# power_regulator_pmic.net
KiCad netlist of a schematic drawn in Altium Designer
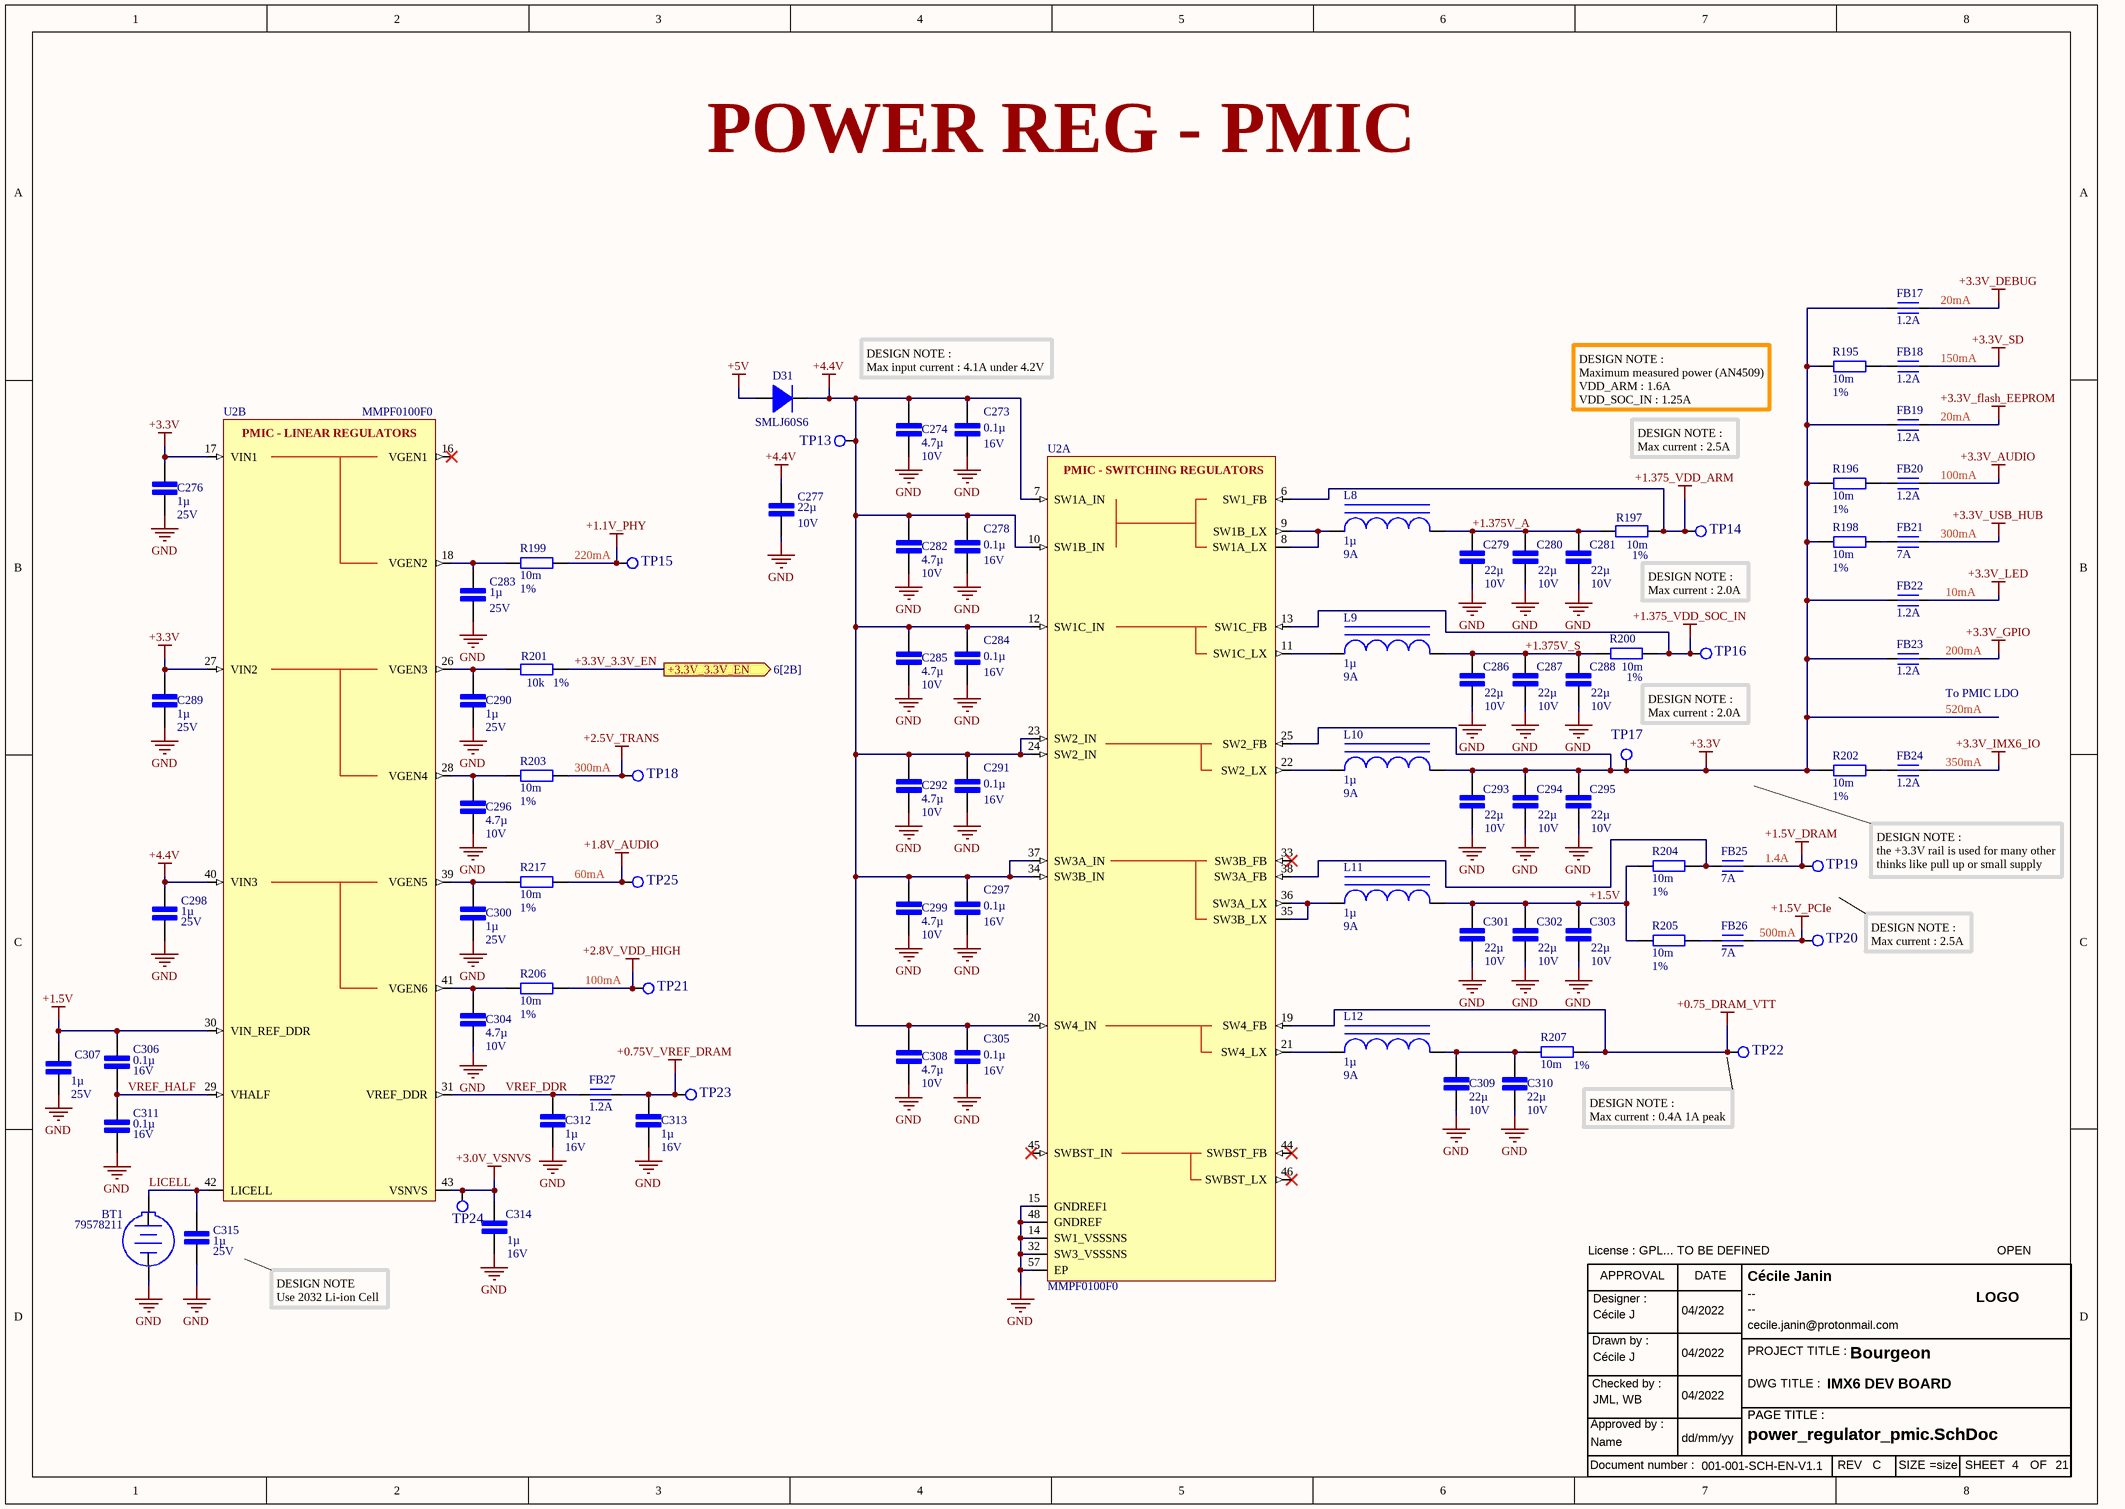
[diagram p0: power_regulator_pmic.SchDoc]

(export (version "E")
  (design (tool "Eeschema 10.0.6"))
  (components
    (comp (ref "BT1")
      (value "79578211")
      (footprint "Battery holder")
      (description "WA-BCPH Battery Holder, THT, Battery Type 2450")
      (fields (field (name "MANUFACTURER") "Wurth Elektronik"))
      (libsource (lib "First Board IMX6") (part "battery holder"))
    )
    (comp (ref "C273")
      (value "0.1µ")
      (footprint "Cap cer 0402/1005")
      (description "cap cer 0.1µ 16V 10% X7R 0402")
      (fields (field (name "TENSION DU DIÉLECTRIQUE") "16V"))
      (libsource (lib "First Board IMX6") (part "cap 0.1µ 4V"))
    )
    (comp (ref "C274")
      (value "4.7µ")
      (footprint "Cap cer 0402/1005")
      (description "cap cer 4.7µ 10V 10% X7R 0402")
      (fields (field (name "TENSION DU DIÉLECTRIQUE") "10V"))
      (libsource (lib "First Board IMX6") (part "cap 4.7µ 10V"))
    )
    (comp (ref "C276")
      (value "1µ")
      (footprint "Cap cer 0402/1005")
      (description "cap cer 1µ 25V 10% X5R 0402")
      (fields (field (name "TENSION DU DIÉLECTRIQUE") "25V"))
      (libsource (lib "First Board IMX6") (part "cap 1µ 25V"))
    )
    (comp (ref "C277")
      (value "22µ")
      (footprint "Cap cer 0603/4608")
      (description "cap cer 22µ 10V 10% X5R 0603")
      (fields (field (name "TENSION DU DIÉLECTRIQUE") "10V"))
      (libsource (lib "First Board IMX6") (part "cap 22µ 10V"))
    )
    (comp (ref "C278")
      (value "0.1µ")
      (footprint "Cap cer 0402/1005")
      (description "cap cer 0.1µ 16V 10% X7R 0402")
      (fields (field (name "TENSION DU DIÉLECTRIQUE") "16V"))
      (libsource (lib "First Board IMX6") (part "cap 0.1µ 4V"))
    )
    (comp (ref "C279")
      (value "22µ")
      (footprint "Cap cer 0603/4608")
      (description "cap cer 22µ 10V 10% X5R 0603")
      (fields (field (name "TENSION DU DIÉLECTRIQUE") "10V"))
      (libsource (lib "First Board IMX6") (part "cap 22µ 10V"))
    )
    (comp (ref "C280")
      (value "22µ")
      (footprint "Cap cer 0603/4608")
      (description "cap cer 22µ 10V 10% X5R 0603")
      (fields (field (name "TENSION DU DIÉLECTRIQUE") "10V"))
      (libsource (lib "First Board IMX6") (part "cap 22µ 10V"))
    )
    (comp (ref "C281")
      (value "22µ")
      (footprint "Cap cer 0603/4608")
      (description "cap cer 22µ 10V 10% X5R 0603")
      (fields (field (name "TENSION DU DIÉLECTRIQUE") "10V"))
      (libsource (lib "First Board IMX6") (part "cap 22µ 10V"))
    )
    (comp (ref "C282")
      (value "4.7µ")
      (footprint "Cap cer 0402/1005")
      (description "cap cer 4.7µ 10V 10% X7R 0402")
      (fields (field (name "TENSION DU DIÉLECTRIQUE") "10V"))
      (libsource (lib "First Board IMX6") (part "cap 4.7µ 10V"))
    )
    (comp (ref "C283")
      (value "1µ")
      (footprint "Cap cer 0402/1005")
      (description "cap cer 1µ 25V 10% X5R 0402")
      (fields (field (name "TENSION DU DIÉLECTRIQUE") "25V"))
      (libsource (lib "First Board IMX6") (part "cap 1µ 25V"))
    )
    (comp (ref "C284")
      (value "0.1µ")
      (footprint "Cap cer 0402/1005")
      (description "cap cer 0.1µ 16V 10% X7R 0402")
      (fields (field (name "TENSION DU DIÉLECTRIQUE") "16V"))
      (libsource (lib "First Board IMX6") (part "cap 0.1µ 4V"))
    )
    (comp (ref "C285")
      (value "4.7µ")
      (footprint "Cap cer 0402/1005")
      (description "cap cer 4.7µ 10V 10% X7R 0402")
      (fields (field (name "TENSION DU DIÉLECTRIQUE") "10V"))
      (libsource (lib "First Board IMX6") (part "cap 4.7µ 10V"))
    )
    (comp (ref "C286")
      (value "22µ")
      (footprint "Cap cer 0603/4608")
      (description "cap cer 22µ 10V 10% X5R 0603")
      (fields (field (name "TENSION DU DIÉLECTRIQUE") "10V"))
      (libsource (lib "First Board IMX6") (part "cap 22µ 10V"))
    )
    (comp (ref "C287")
      (value "22µ")
      (footprint "Cap cer 0603/4608")
      (description "cap cer 22µ 10V 10% X5R 0603")
      (fields (field (name "TENSION DU DIÉLECTRIQUE") "10V"))
      (libsource (lib "First Board IMX6") (part "cap 22µ 10V"))
    )
    (comp (ref "C288")
      (value "22µ")
      (footprint "Cap cer 0603/4608")
      (description "cap cer 22µ 10V 10% X5R 0603")
      (fields (field (name "TENSION DU DIÉLECTRIQUE") "10V"))
      (libsource (lib "First Board IMX6") (part "cap 22µ 10V"))
    )
    (comp (ref "C289")
      (value "1µ")
      (footprint "Cap cer 0402/1005")
      (description "cap cer 1µ 25V 10% X5R 0402")
      (fields (field (name "TENSION DU DIÉLECTRIQUE") "25V"))
      (libsource (lib "First Board IMX6") (part "cap 1µ 25V"))
    )
    (comp (ref "C290")
      (value "1µ")
      (footprint "Cap cer 0402/1005")
      (description "cap cer 1µ 25V 10% X5R 0402")
      (fields (field (name "TENSION DU DIÉLECTRIQUE") "25V"))
      (libsource (lib "First Board IMX6") (part "cap 1µ 25V"))
    )
    (comp (ref "C291")
      (value "0.1µ")
      (footprint "Cap cer 0402/1005")
      (description "cap cer 0.1µ 16V 10% X7R 0402")
      (fields (field (name "TENSION DU DIÉLECTRIQUE") "16V"))
      (libsource (lib "First Board IMX6") (part "cap 0.1µ 4V"))
    )
    (comp (ref "C292")
      (value "4.7µ")
      (footprint "Cap cer 0402/1005")
      (description "cap cer 4.7µ 10V 10% X7R 0402")
      (fields (field (name "TENSION DU DIÉLECTRIQUE") "10V"))
      (libsource (lib "First Board IMX6") (part "cap 4.7µ 10V"))
    )
    (comp (ref "C293")
      (value "22µ")
      (footprint "Cap cer 0603/4608")
      (description "cap cer 22µ 10V 10% X5R 0603")
      (fields (field (name "TENSION DU DIÉLECTRIQUE") "10V"))
      (libsource (lib "First Board IMX6") (part "cap 22µ 10V"))
    )
    (comp (ref "C294")
      (value "22µ")
      (footprint "Cap cer 0603/4608")
      (description "cap cer 22µ 10V 10% X5R 0603")
      (fields (field (name "TENSION DU DIÉLECTRIQUE") "10V"))
      (libsource (lib "First Board IMX6") (part "cap 22µ 10V"))
    )
    (comp (ref "C295")
      (value "22µ")
      (footprint "Cap cer 0603/4608")
      (description "cap cer 22µ 10V 10% X5R 0603")
      (fields (field (name "TENSION DU DIÉLECTRIQUE") "10V"))
      (libsource (lib "First Board IMX6") (part "cap 22µ 10V"))
    )
    (comp (ref "C296")
      (value "4.7µ")
      (footprint "Cap cer 0402/1005")
      (description "cap cer 4.7µ 10V 10% X7R 0402")
      (fields (field (name "TENSION DU DIÉLECTRIQUE") "10V"))
      (libsource (lib "First Board IMX6") (part "cap 4.7µ 10V"))
    )
    (comp (ref "C297")
      (value "0.1µ")
      (footprint "Cap cer 0402/1005")
      (description "cap cer 0.1µ 16V 10% X7R 0402")
      (fields (field (name "TENSION DU DIÉLECTRIQUE") "16V"))
      (libsource (lib "First Board IMX6") (part "cap 0.1µ 4V"))
    )
    (comp (ref "C298")
      (value "1µ")
      (footprint "Cap cer 0402/1005")
      (description "cap cer 1µ 25V 10% X5R 0402")
      (fields (field (name "TENSION DU DIÉLECTRIQUE") "25V"))
      (libsource (lib "First Board IMX6") (part "cap 1µ 25V"))
    )
    (comp (ref "C299")
      (value "4.7µ")
      (footprint "Cap cer 0402/1005")
      (description "cap cer 4.7µ 10V 10% X7R 0402")
      (fields (field (name "TENSION DU DIÉLECTRIQUE") "10V"))
      (libsource (lib "First Board IMX6") (part "cap 4.7µ 10V"))
    )
    (comp (ref "C300")
      (value "1µ")
      (footprint "Cap cer 0402/1005")
      (description "cap cer 1µ 25V 10% X5R 0402")
      (fields (field (name "TENSION DU DIÉLECTRIQUE") "25V"))
      (libsource (lib "First Board IMX6") (part "cap 1µ 25V"))
    )
    (comp (ref "C301")
      (value "22µ")
      (footprint "Cap cer 0603/4608")
      (description "cap cer 22µ 10V 10% X5R 0603")
      (fields (field (name "TENSION DU DIÉLECTRIQUE") "10V"))
      (libsource (lib "First Board IMX6") (part "cap 22µ 10V"))
    )
    (comp (ref "C302")
      (value "22µ")
      (footprint "Cap cer 0603/4608")
      (description "cap cer 22µ 10V 10% X5R 0603")
      (fields (field (name "TENSION DU DIÉLECTRIQUE") "10V"))
      (libsource (lib "First Board IMX6") (part "cap 22µ 10V"))
    )
    (comp (ref "C303")
      (value "22µ")
      (footprint "Cap cer 0603/4608")
      (description "cap cer 22µ 10V 10% X5R 0603")
      (fields (field (name "TENSION DU DIÉLECTRIQUE") "10V"))
      (libsource (lib "First Board IMX6") (part "cap 22µ 10V"))
    )
    (comp (ref "C304")
      (value "4.7µ")
      (footprint "Cap cer 0402/1005")
      (description "cap cer 4.7µ 10V 10% X7R 0402")
      (fields (field (name "TENSION DU DIÉLECTRIQUE") "10V"))
      (libsource (lib "First Board IMX6") (part "cap 4.7µ 10V"))
    )
    (comp (ref "C305")
      (value "0.1µ")
      (footprint "Cap cer 0402/1005")
      (description "cap cer 0.1µ 16V 10% X7R 0402")
      (fields (field (name "TENSION DU DIÉLECTRIQUE") "16V"))
      (libsource (lib "First Board IMX6") (part "cap 0.1µ 4V"))
    )
    (comp (ref "C306")
      (value "0.1µ")
      (footprint "Cap cer 0402/1005")
      (description "cap solid electrolyte 0.1µ 6.3V 10%")
      (fields (field (name "TENSION DU DIÉLECTRIQUE") "16V"))
      (libsource (lib "First Board IMX6") (part "cap 0.1µ 16V"))
    )
    (comp (ref "C307")
      (value "1µ")
      (footprint "Cap cer 0402/1005")
      (description "cap cer 1µ 25V 10% X5R 0402")
      (fields (field (name "TENSION DU DIÉLECTRIQUE") "25V"))
      (libsource (lib "First Board IMX6") (part "cap 1µ 25V"))
    )
    (comp (ref "C308")
      (value "4.7µ")
      (footprint "Cap cer 0402/1005")
      (description "cap cer 4.7µ 10V 10% X7R 0402")
      (fields (field (name "TENSION DU DIÉLECTRIQUE") "10V"))
      (libsource (lib "First Board IMX6") (part "cap 4.7µ 10V"))
    )
    (comp (ref "C309")
      (value "22µ")
      (footprint "Cap cer 0603/4608")
      (description "cap cer 22µ 10V 10% X5R 0603")
      (fields (field (name "TENSION DU DIÉLECTRIQUE") "10V"))
      (libsource (lib "First Board IMX6") (part "cap 22µ 10V"))
    )
    (comp (ref "C310")
      (value "22µ")
      (footprint "Cap cer 0603/4608")
      (description "cap cer 22µ 10V 10% X5R 0603")
      (fields (field (name "TENSION DU DIÉLECTRIQUE") "10V"))
      (libsource (lib "First Board IMX6") (part "cap 22µ 10V"))
    )
    (comp (ref "C311")
      (value "0.1µ")
      (footprint "Cap cer 0402/1005")
      (description "cap solid electrolyte 0.1µ 6.3V 10%")
      (fields (field (name "TENSION DU DIÉLECTRIQUE") "16V"))
      (libsource (lib "First Board IMX6") (part "cap 0.1µ 16V"))
    )
    (comp (ref "C312")
      (value "1µ")
      (footprint "Cap cer 0402/1005")
      (description "cap cer 1µ 16V 10% X7R 0402")
      (fields (field (name "TENSION DU DIÉLECTRIQUE") "16V"))
      (libsource (lib "First Board IMX6") (part "cap 1µ 16V"))
    )
    (comp (ref "C313")
      (value "1µ")
      (footprint "Cap cer 0402/1005")
      (description "cap cer 1µ 16V 10% X7R 0402")
      (fields (field (name "TENSION DU DIÉLECTRIQUE") "16V"))
      (libsource (lib "First Board IMX6") (part "cap 1µ 16V"))
    )
    (comp (ref "C314")
      (value "1µ")
      (footprint "Cap cer 0402/1005")
      (description "cap cer 1µ 16V 10% X7R 0402")
      (fields (field (name "TENSION DU DIÉLECTRIQUE") "16V"))
      (libsource (lib "First Board IMX6") (part "cap 1µ 16V"))
    )
    (comp (ref "C315")
      (value "1µ")
      (footprint "Cap cer 0402/1005")
      (description "cap cer 1µ 25V 10% X5R 0402")
      (fields (field (name "TENSION DU DIÉLECTRIQUE") "25V"))
      (libsource (lib "First Board IMX6") (part "cap 1µ 25V"))
    )
    (comp (ref "D31")
      (value "SMLJ60S6")
      (footprint "DO-214AB")
      (description "Diode 600V 6A DO-214AB")
      (libsource (lib "First Board IMX6") (part "Diode 600V 6A"))
    )
    (comp (ref "FB17")
      (value "1.2A")
      (footprint "inductor 0402/1005")
      (description "ferrite bead 1.2A 70mohm\r\n74269242111")
      (libsource (lib "First Board IMX6") (part "Ferrite bead 0402"))
    )
    (comp (ref "FB18")
      (value "1.2A")
      (footprint "inductor 0402/1005")
      (description "ferrite bead 1.2A 70mohm\r\n74269242111")
      (libsource (lib "First Board IMX6") (part "Ferrite bead 0402"))
    )
    (comp (ref "FB19")
      (value "1.2A")
      (footprint "inductor 0402/1005")
      (description "ferrite bead 1.2A 70mohm\r\n74269242111")
      (libsource (lib "First Board IMX6") (part "Ferrite bead 0402"))
    )
    (comp (ref "FB20")
      (value "1.2A")
      (footprint "inductor 0402/1005")
      (description "ferrite bead 1.2A 70mohm\r\n74269242111")
      (libsource (lib "First Board IMX6") (part "Ferrite bead 0402"))
    )
    (comp (ref "FB21")
      (value "7A")
      (footprint "inductor 0603/1603")
      (description "ferrite bead 17AA 2mohm\r\n7426926222")
      (libsource (lib "First Board IMX6") (part "Ferrite bead 0603"))
    )
    (comp (ref "FB22")
      (value "1.2A")
      (footprint "inductor 0402/1005")
      (description "ferrite bead 1.2A 70mohm\r\n74269242111")
      (libsource (lib "First Board IMX6") (part "Ferrite bead 0402"))
    )
    (comp (ref "FB23")
      (value "1.2A")
      (footprint "inductor 0402/1005")
      (description "ferrite bead 1.2A 70mohm\r\n74269242111")
      (libsource (lib "First Board IMX6") (part "Ferrite bead 0402"))
    )
    (comp (ref "FB24")
      (value "1.2A")
      (footprint "inductor 0402/1005")
      (description "ferrite bead 1.2A 70mohm\r\n74269242111")
      (libsource (lib "First Board IMX6") (part "Ferrite bead 0402"))
    )
    (comp (ref "FB25")
      (value "7A")
      (footprint "inductor 0603/1603")
      (description "ferrite bead 17AA 2mohm\r\n7426926222")
      (libsource (lib "First Board IMX6") (part "Ferrite bead 0603"))
    )
    (comp (ref "FB26")
      (value "7A")
      (footprint "inductor 0603/1603")
      (description "ferrite bead 17AA 2mohm\r\n7426926222")
      (libsource (lib "First Board IMX6") (part "Ferrite bead 0603"))
    )
    (comp (ref "FB27")
      (value "1.2A")
      (footprint "inductor 0402/1005")
      (description "ferrite bead 1.2A 70mohm\r\n74269242111")
      (libsource (lib "First Board IMX6") (part "Ferrite bead 0402"))
    )
    (comp (ref "L8")
      (value "1µ")
      (footprint "inductor 4020 MAPI")
      (description "inductor 1.0µ 9A sat 4020 74438356010")
      (fields (field (name "SATURATION") "9A"))
      (libsource (lib "First Board IMX6") (part "inductor 1.0µ 9A"))
    )
    (comp (ref "L9")
      (value "1µ")
      (footprint "inductor 4020 MAPI")
      (description "inductor 1.0µ 9A sat 4020 74438356010")
      (fields (field (name "SATURATION") "9A"))
      (libsource (lib "First Board IMX6") (part "inductor 1.0µ 9A"))
    )
    (comp (ref "L10")
      (value "1µ")
      (footprint "inductor 4020 MAPI")
      (description "inductor 1.0µ 9A sat 4020 74438356010")
      (fields (field (name "SATURATION") "9A"))
      (libsource (lib "First Board IMX6") (part "inductor 1.0µ 9A"))
    )
    (comp (ref "L11")
      (value "1µ")
      (footprint "inductor 4020 MAPI")
      (description "inductor 1.0µ 9A sat 4020 74438356010")
      (fields (field (name "SATURATION") "9A"))
      (libsource (lib "First Board IMX6") (part "inductor 1.0µ 9A"))
    )
    (comp (ref "L12")
      (value "1µ")
      (footprint "inductor 4020 MAPI")
      (description "inductor 1.0µ 9A sat 4020 74438356010")
      (fields (field (name "SATURATION") "9A"))
      (libsource (lib "First Board IMX6") (part "inductor 1.0µ 9A"))
    )
    (comp (ref "R195")
      (value "10m")
      (footprint "Res 0603/1603")
      (description "res 10m 1% 0.33W 0603")
      (fields (field (name "POURCENTAGE") "1%"))
      (libsource (lib "First Board IMX6") (part "res 10m 1%"))
    )
    (comp (ref "R196")
      (value "10m")
      (footprint "Res 0603/1603")
      (description "res 10m 1% 0.33W 0603")
      (fields (field (name "POURCENTAGE") "1%"))
      (libsource (lib "First Board IMX6") (part "res 10m 1%"))
    )
    (comp (ref "R197")
      (value "10m")
      (footprint "Res 0603/1603")
      (description "res 10m 1% 0.33W 0603")
      (fields (field (name "POURCENTAGE") "1%"))
      (libsource (lib "First Board IMX6") (part "res 10m 1%"))
    )
    (comp (ref "R198")
      (value "10m")
      (footprint "Res 0603/1603")
      (description "res 10m 1% 0.33W 0603")
      (fields (field (name "POURCENTAGE") "1%"))
      (libsource (lib "First Board IMX6") (part "res 10m 1%"))
    )
    (comp (ref "R199")
      (value "10m")
      (footprint "Res 0603/1603")
      (description "res 10m 1% 0.33W 0603")
      (fields (field (name "POURCENTAGE") "1%"))
      (libsource (lib "First Board IMX6") (part "res 10m 1%"))
    )
    (comp (ref "R200")
      (value "10m")
      (footprint "Res 0603/1603")
      (description "res 10m 1% 0.33W 0603")
      (fields (field (name "POURCENTAGE") "1%"))
      (libsource (lib "First Board IMX6") (part "res 10m 1%"))
    )
    (comp (ref "R201")
      (value "10k")
      (footprint "Res 0402/1005")
      (description "res 10k 1% 0402")
      (fields (field (name "POURCENTAGE") "1%"))
      (libsource (lib "First Board IMX6") (part "res 10k 1%"))
    )
    (comp (ref "R202")
      (value "10m")
      (footprint "Res 0603/1603")
      (description "res 10m 1% 0.33W 0603")
      (fields (field (name "POURCENTAGE") "1%"))
      (libsource (lib "First Board IMX6") (part "res 10m 1%"))
    )
    (comp (ref "R203")
      (value "10m")
      (footprint "Res 0603/1603")
      (description "res 10m 1% 0.33W 0603")
      (fields (field (name "POURCENTAGE") "1%"))
      (libsource (lib "First Board IMX6") (part "res 10m 1%"))
    )
    (comp (ref "R204")
      (value "10m")
      (footprint "Res 0603/1603")
      (description "res 10m 1% 0.33W 0603")
      (fields (field (name "POURCENTAGE") "1%"))
      (libsource (lib "First Board IMX6") (part "res 10m 1%"))
    )
    (comp (ref "R205")
      (value "10m")
      (footprint "Res 0603/1603")
      (description "res 10m 1% 0.33W 0603")
      (fields (field (name "POURCENTAGE") "1%"))
      (libsource (lib "First Board IMX6") (part "res 10m 1%"))
    )
    (comp (ref "R206")
      (value "10m")
      (footprint "Res 0603/1603")
      (description "res 10m 1% 0.33W 0603")
      (fields (field (name "POURCENTAGE") "1%"))
      (libsource (lib "First Board IMX6") (part "res 10m 1%"))
    )
    (comp (ref "R207")
      (value "10m")
      (footprint "Res 0603/1603")
      (description "res 10m 1% 0.33W 0603")
      (fields (field (name "POURCENTAGE") "1%"))
      (libsource (lib "First Board IMX6") (part "res 10m 1%"))
    )
    (comp (ref "R217")
      (value "10m")
      (footprint "Res 0603/1603")
      (description "res 10m 1% 0.33W 0603")
      (fields (field (name "POURCENTAGE") "1%"))
      (libsource (lib "First Board IMX6") (part "res 10m 1%"))
    )
    (comp (ref "TB21")
      (value "Title bloc ANSI modified")
      (libsource (lib "First Board IMX6") (part "Title bloc ANSI"))
    )
    (comp (ref "TP13")
      (value "Test Point")
      (footprint "testpoint 1mm")
      (description "Test point 1mm diameter")
      (libsource (lib "First Board IMX6") (part "Test Point"))
    )
    (comp (ref "TP14")
      (value "Test Point")
      (footprint "testpoint 1mm")
      (description "Test point 1mm diameter")
      (libsource (lib "First Board IMX6") (part "Test Point"))
    )
    (comp (ref "TP15")
      (value "Test Point")
      (footprint "testpoint 1mm")
      (description "Test point 1mm diameter")
      (libsource (lib "First Board IMX6") (part "Test Point"))
    )
    (comp (ref "TP16")
      (value "Test Point")
      (footprint "testpoint 1mm")
      (description "Test point 1mm diameter")
      (libsource (lib "First Board IMX6") (part "Test Point"))
    )
    (comp (ref "TP17")
      (value "Test Point")
      (footprint "testpoint 1mm")
      (description "Test point 1mm diameter")
      (libsource (lib "First Board IMX6") (part "Test Point"))
    )
    (comp (ref "TP18")
      (value "Test Point")
      (footprint "testpoint 1mm")
      (description "Test point 1mm diameter")
      (libsource (lib "First Board IMX6") (part "Test Point"))
    )
    (comp (ref "TP19")
      (value "Test Point")
      (footprint "testpoint 1mm")
      (description "Test point 1mm diameter")
      (libsource (lib "First Board IMX6") (part "Test Point"))
    )
    (comp (ref "TP20")
      (value "Test Point")
      (footprint "testpoint 1mm")
      (description "Test point 1mm diameter")
      (libsource (lib "First Board IMX6") (part "Test Point"))
    )
    (comp (ref "TP21")
      (value "Test Point")
      (footprint "testpoint 1mm")
      (description "Test point 1mm diameter")
      (libsource (lib "First Board IMX6") (part "Test Point"))
    )
    (comp (ref "TP22")
      (value "Test Point")
      (footprint "testpoint 1mm")
      (description "Test point 1mm diameter")
      (libsource (lib "First Board IMX6") (part "Test Point"))
    )
    (comp (ref "TP23")
      (value "Test Point")
      (footprint "testpoint 1mm")
      (description "Test point 1mm diameter")
      (libsource (lib "First Board IMX6") (part "Test Point"))
    )
    (comp (ref "TP24")
      (value "Test Point")
      (footprint "testpoint 1mm")
      (description "Test point 1mm diameter")
      (libsource (lib "First Board IMX6") (part "Test Point"))
    )
    (comp (ref "TP25")
      (value "Test Point")
      (footprint "testpoint 1mm")
      (description "Test point 1mm diameter")
      (libsource (lib "First Board IMX6") (part "Test Point"))
    )
    (comp (ref "U2")
      (value "MMPF0100F0")
      (footprint "MMPF0100")
      (description "PMIC")
      (libsource (lib "First Board IMX6") (part "IC MMPF0100"))
    )
  )
  (nets
    (net (code "1") (name "+0.75V_VREF_DRAM") (class "Default")
      (node (ref "C313") (pin "1") (pinfunction "3_1") (pintype "passive"))
      (node (ref "FB27") (pin "2") (pinfunction "2_2") (pintype "passive"))
      (node (ref "TP23") (pin "1") (pinfunction "tp_1") (pintype "passive"))
    )
    (net (code "2") (name "+0.75_DRAM_VTT") (class "Default")
      (node (ref "R207") (pin "2") (pintype "passive"))
      (node (ref "TP22") (pin "1") (pinfunction "tp_1") (pintype "passive"))
      (node (ref "U2") (pin "19") (pinfunction "SW4_FB_19") (pintype "input"))
    )
    (net (code "3") (name "+1.1V_PHY") (class "Default")
      (node (ref "R199") (pin "2") (pintype "passive"))
      (node (ref "TP15") (pin "1") (pinfunction "tp_1") (pintype "passive"))
    )
    (net (code "4") (name "+1.5V") (class "Default")
      (node (ref "C301") (pin "1") (pinfunction "3_1") (pintype "passive"))
      (node (ref "C302") (pin "1") (pinfunction "3_1") (pintype "passive"))
      (node (ref "C303") (pin "1") (pinfunction "3_1") (pintype "passive"))
      (node (ref "C306") (pin "1") (pinfunction "3_1") (pintype "passive"))
      (node (ref "C307") (pin "1") (pinfunction "3_1") (pintype "passive"))
      (node (ref "L11") (pin "2") (pintype "passive"))
      (node (ref "R204") (pin "1") (pintype "passive"))
      (node (ref "R205") (pin "1") (pintype "passive"))
      (node (ref "U2") (pin "30") (pinfunction "VIN_REF_DDR_30") (pintype "input"))
    )
    (net (code "5") (name "+1.5V_DRAM") (class "Default")
      (node (ref "FB25") (pin "2") (pinfunction "2_2") (pintype "passive"))
      (node (ref "TP19") (pin "1") (pinfunction "tp_1") (pintype "passive"))
    )
    (net (code "6") (name "+1.5V_PCIe") (class "Default")
      (node (ref "FB26") (pin "2") (pinfunction "2_2") (pintype "passive"))
      (node (ref "TP20") (pin "1") (pinfunction "tp_1") (pintype "passive"))
    )
    (net (code "7") (name "+1.8V_AUDIO") (class "Default")
      (node (ref "R217") (pin "2") (pintype "passive"))
      (node (ref "TP25") (pin "1") (pinfunction "tp_1") (pintype "passive"))
    )
    (net (code "8") (name "+1.375_VDD_ARM") (class "Default")
      (node (ref "R197") (pin "2") (pintype "passive"))
      (node (ref "TP14") (pin "1") (pinfunction "tp_1") (pintype "passive"))
      (node (ref "U2") (pin "6") (pinfunction "SW1_FB_6") (pintype "input"))
    )
    (net (code "9") (name "+1.375_VDD_SOC_IN") (class "Default")
      (node (ref "R200") (pin "2") (pintype "passive"))
      (node (ref "TP16") (pin "1") (pinfunction "tp_1") (pintype "passive"))
      (node (ref "U2") (pin "13") (pinfunction "SW1C_FB_13") (pintype "input"))
    )
    (net (code "10") (name "+2.5V_TRANS") (class "Default")
      (node (ref "R203") (pin "2") (pintype "passive"))
      (node (ref "TP18") (pin "1") (pinfunction "tp_1") (pintype "passive"))
    )
    (net (code "11") (name "+2.8V_VDD_HIGH") (class "Default")
      (node (ref "R206") (pin "2") (pintype "passive"))
      (node (ref "TP21") (pin "1") (pinfunction "tp_1") (pintype "passive"))
    )
    (net (code "12") (name "+3.0V_VSNVS") (class "Default")
      (node (ref "C314") (pin "1") (pinfunction "3_1") (pintype "passive"))
      (node (ref "TP24") (pin "1") (pinfunction "tp_1") (pintype "passive"))
      (node (ref "U2") (pin "43") (pinfunction "VSNVS_43") (pintype "bidirectional"))
    )
    (net (code "13") (name "+3.3V") (class "Default")
      (node (ref "C276") (pin "1") (pinfunction "3_1") (pintype "passive"))
      (node (ref "C289") (pin "1") (pinfunction "3_1") (pintype "passive"))
      (node (ref "C293") (pin "1") (pinfunction "3_1") (pintype "passive"))
      (node (ref "C294") (pin "1") (pinfunction "3_1") (pintype "passive"))
      (node (ref "C295") (pin "1") (pinfunction "3_1") (pintype "passive"))
      (node (ref "FB17") (pin "1") (pinfunction "1_1") (pintype "passive"))
      (node (ref "FB19") (pin "1") (pinfunction "1_1") (pintype "passive"))
      (node (ref "FB22") (pin "1") (pinfunction "1_1") (pintype "passive"))
      (node (ref "FB23") (pin "1") (pinfunction "1_1") (pintype "passive"))
      (node (ref "L10") (pin "2") (pintype "passive"))
      (node (ref "R195") (pin "2") (pintype "passive"))
      (node (ref "R196") (pin "1") (pintype "passive"))
      (node (ref "R198") (pin "2") (pintype "passive"))
      (node (ref "R202") (pin "1") (pintype "passive"))
      (node (ref "TP17") (pin "1") (pinfunction "tp_1") (pintype "passive"))
      (node (ref "U2") (pin "17") (pinfunction "VIN1_17") (pintype "input"))
      (node (ref "U2") (pin "25") (pinfunction "SW2_FB_25") (pintype "input"))
      (node (ref "U2") (pin "27") (pinfunction "VIN2_27") (pintype "input"))
    )
    (net (code "14") (name "+3.3V_AUDIO") (class "Default")
      (node (ref "FB20") (pin "2") (pinfunction "2_2") (pintype "passive"))
    )
    (net (code "15") (name "+3.3V_DEBUG") (class "Default")
      (node (ref "FB17") (pin "2") (pinfunction "2_2") (pintype "passive"))
    )
    (net (code "16") (name "+3.3V_GPIO") (class "Default")
      (node (ref "FB23") (pin "2") (pinfunction "2_2") (pintype "passive"))
    )
    (net (code "17") (name "+3.3V_IMX6_IO") (class "Default")
      (node (ref "FB24") (pin "2") (pinfunction "2_2") (pintype "passive"))
    )
    (net (code "18") (name "+3.3V_LED") (class "Default")
      (node (ref "FB22") (pin "2") (pinfunction "2_2") (pintype "passive"))
    )
    (net (code "19") (name "+3.3V_SD") (class "Default")
      (node (ref "FB18") (pin "2") (pinfunction "2_2") (pintype "passive"))
    )
    (net (code "20") (name "+3.3V_USB_HUB") (class "Default")
      (node (ref "FB21") (pin "2") (pinfunction "2_2") (pintype "passive"))
    )
    (net (code "21") (name "+3.3V_flash_EEPROM") (class "Default")
      (node (ref "FB19") (pin "2") (pinfunction "2_2") (pintype "passive"))
    )
    (net (code "22") (name "+4.4V") (class "Default")
      (node (ref "C273") (pin "1") (pinfunction "3_1") (pintype "passive"))
      (node (ref "C274") (pin "1") (pinfunction "3_1") (pintype "passive"))
      (node (ref "C277") (pin "1") (pinfunction "3_1") (pintype "passive"))
      (node (ref "C278") (pin "1") (pinfunction "3_1") (pintype "passive"))
      (node (ref "C282") (pin "1") (pinfunction "3_1") (pintype "passive"))
      (node (ref "C284") (pin "1") (pinfunction "3_1") (pintype "passive"))
      (node (ref "C285") (pin "1") (pinfunction "3_1") (pintype "passive"))
      (node (ref "C291") (pin "1") (pinfunction "3_1") (pintype "passive"))
      (node (ref "C292") (pin "1") (pinfunction "3_1") (pintype "passive"))
      (node (ref "C297") (pin "1") (pinfunction "3_1") (pintype "passive"))
      (node (ref "C298") (pin "1") (pinfunction "3_1") (pintype "passive"))
      (node (ref "C299") (pin "1") (pinfunction "3_1") (pintype "passive"))
      (node (ref "C305") (pin "1") (pinfunction "3_1") (pintype "passive"))
      (node (ref "C308") (pin "1") (pinfunction "3_1") (pintype "passive"))
      (node (ref "D31") (pin "K") (pintype "passive"))
      (node (ref "TP13") (pin "1") (pinfunction "tp_1") (pintype "passive"))
      (node (ref "U2") (pin "10") (pinfunction "SW1B_IN_10") (pintype "input"))
      (node (ref "U2") (pin "12") (pinfunction "SW1C_IN_12") (pintype "input"))
      (node (ref "U2") (pin "20") (pinfunction "SW4_IN_20") (pintype "input"))
      (node (ref "U2") (pin "23") (pinfunction "SW2_IN_23") (pintype "input"))
      (node (ref "U2") (pin "24") (pinfunction "SW2_IN_24") (pintype "input"))
      (node (ref "U2") (pin "34") (pinfunction "SW3B_IN_34") (pintype "input"))
      (node (ref "U2") (pin "37") (pinfunction "SW3A_IN_37") (pintype "input"))
      (node (ref "U2") (pin "40") (pinfunction "VIN3_40") (pintype "input"))
      (node (ref "U2") (pin "7") (pinfunction "SW1A_IN_7") (pintype "input"))
    )
    (net (code "23") (name "+5V") (class "Default") (node (ref "D31") (pin "A") (pintype "passive")))
    (net (code "24") (name "/+1.375V_A") (class "Default")
      (node (ref "C279") (pin "1") (pinfunction "3_1") (pintype "passive"))
      (node (ref "C280") (pin "1") (pinfunction "3_1") (pintype "passive"))
      (node (ref "C281") (pin "1") (pinfunction "3_1") (pintype "passive"))
      (node (ref "L8") (pin "2") (pintype "passive"))
      (node (ref "R197") (pin "1") (pintype "passive"))
    )
    (net (code "25") (name "/+1.375V_S") (class "Default")
      (node (ref "C286") (pin "1") (pinfunction "3_1") (pintype "passive"))
      (node (ref "C287") (pin "1") (pinfunction "3_1") (pintype "passive"))
      (node (ref "C288") (pin "1") (pinfunction "3_1") (pintype "passive"))
      (node (ref "L9") (pin "2") (pintype "passive"))
      (node (ref "R200") (pin "1") (pintype "passive"))
    )
    (net (code "26") (name "/+3.3V_3.3V_EN") (class "Default")
      (node (ref "R201") (pin "2") (pintype "passive"))
    )
    (net (code "27") (name "/LICELL") (class "Default")
      (node (ref "BT1") (pin "1") (pinfunction "+_1") (pintype "passive"))
      (node (ref "C315") (pin "1") (pinfunction "3_1") (pintype "passive"))
      (node (ref "U2") (pin "42") (pinfunction "LICELL_42") (pintype "bidirectional"))
    )
    (net (code "28") (name "/VREF_DDR") (class "Default")
      (node (ref "C312") (pin "1") (pinfunction "3_1") (pintype "passive"))
      (node (ref "FB27") (pin "1") (pinfunction "1_1") (pintype "passive"))
      (node (ref "U2") (pin "31") (pinfunction "VREF_DDR_31") (pintype "output"))
    )
    (net (code "29") (name "/VREF_HALF") (class "Default")
      (node (ref "C306") (pin "2") (pinfunction "4_2") (pintype "passive"))
      (node (ref "C311") (pin "1") (pinfunction "3_1") (pintype "passive"))
      (node (ref "U2") (pin "29") (pinfunction "VHALF_29") (pintype "input"))
    )
    (net (code "30") (name "GND") (class "Default")
      (node (ref "BT1") (pin "2") (pinfunction "-_2") (pintype "passive"))
      (node (ref "C273") (pin "2") (pinfunction "4_2") (pintype "passive"))
      (node (ref "C274") (pin "2") (pinfunction "4_2") (pintype "passive"))
      (node (ref "C276") (pin "2") (pinfunction "4_2") (pintype "passive"))
      (node (ref "C277") (pin "2") (pinfunction "4_2") (pintype "passive"))
      (node (ref "C278") (pin "2") (pinfunction "4_2") (pintype "passive"))
      (node (ref "C279") (pin "2") (pinfunction "4_2") (pintype "passive"))
      (node (ref "C280") (pin "2") (pinfunction "4_2") (pintype "passive"))
      (node (ref "C281") (pin "2") (pinfunction "4_2") (pintype "passive"))
      (node (ref "C282") (pin "2") (pinfunction "4_2") (pintype "passive"))
      (node (ref "C283") (pin "2") (pinfunction "4_2") (pintype "passive"))
      (node (ref "C284") (pin "2") (pinfunction "4_2") (pintype "passive"))
      (node (ref "C285") (pin "2") (pinfunction "4_2") (pintype "passive"))
      (node (ref "C286") (pin "2") (pinfunction "4_2") (pintype "passive"))
      (node (ref "C287") (pin "2") (pinfunction "4_2") (pintype "passive"))
      (node (ref "C288") (pin "2") (pinfunction "4_2") (pintype "passive"))
      (node (ref "C289") (pin "2") (pinfunction "4_2") (pintype "passive"))
      (node (ref "C290") (pin "2") (pinfunction "4_2") (pintype "passive"))
      (node (ref "C291") (pin "2") (pinfunction "4_2") (pintype "passive"))
      (node (ref "C292") (pin "2") (pinfunction "4_2") (pintype "passive"))
      (node (ref "C293") (pin "2") (pinfunction "4_2") (pintype "passive"))
      (node (ref "C294") (pin "2") (pinfunction "4_2") (pintype "passive"))
      (node (ref "C295") (pin "2") (pinfunction "4_2") (pintype "passive"))
      (node (ref "C296") (pin "2") (pinfunction "4_2") (pintype "passive"))
      (node (ref "C297") (pin "2") (pinfunction "4_2") (pintype "passive"))
      (node (ref "C298") (pin "2") (pinfunction "4_2") (pintype "passive"))
      (node (ref "C299") (pin "2") (pinfunction "4_2") (pintype "passive"))
      (node (ref "C300") (pin "2") (pinfunction "4_2") (pintype "passive"))
      (node (ref "C301") (pin "2") (pinfunction "4_2") (pintype "passive"))
      (node (ref "C302") (pin "2") (pinfunction "4_2") (pintype "passive"))
      (node (ref "C303") (pin "2") (pinfunction "4_2") (pintype "passive"))
      (node (ref "C304") (pin "2") (pinfunction "4_2") (pintype "passive"))
      (node (ref "C305") (pin "2") (pinfunction "4_2") (pintype "passive"))
      (node (ref "C307") (pin "2") (pinfunction "4_2") (pintype "passive"))
      (node (ref "C308") (pin "2") (pinfunction "4_2") (pintype "passive"))
      (node (ref "C309") (pin "2") (pinfunction "4_2") (pintype "passive"))
      (node (ref "C310") (pin "2") (pinfunction "4_2") (pintype "passive"))
      (node (ref "C311") (pin "2") (pinfunction "4_2") (pintype "passive"))
      (node (ref "C312") (pin "2") (pinfunction "4_2") (pintype "passive"))
      (node (ref "C313") (pin "2") (pinfunction "4_2") (pintype "passive"))
      (node (ref "C314") (pin "2") (pinfunction "4_2") (pintype "passive"))
      (node (ref "C315") (pin "2") (pinfunction "4_2") (pintype "passive"))
      (node (ref "U2") (pin "14") (pinfunction "SW1_VSSSNS_14") (pintype "passive"))
      (node (ref "U2") (pin "15") (pinfunction "GNDREF1_15") (pintype "passive"))
      (node (ref "U2") (pin "32") (pinfunction "SW3_VSSSNS_32") (pintype "passive"))
      (node (ref "U2") (pin "48") (pinfunction "GNDREF_48") (pintype "passive"))
      (node (ref "U2") (pin "57") (pinfunction "EP_57") (pintype "passive"))
    )
    (net (code "31") (name "Net-(C283-3)") (class "Default")
      (node (ref "C283") (pin "1") (pinfunction "3_1") (pintype "passive"))
      (node (ref "R199") (pin "1") (pintype "passive"))
      (node (ref "U2") (pin "18") (pinfunction "VGEN2_18") (pintype "output"))
    )
    (net (code "32") (name "Net-(C290-3)") (class "Default")
      (node (ref "C290") (pin "1") (pinfunction "3_1") (pintype "passive"))
      (node (ref "R201") (pin "1") (pintype "passive"))
      (node (ref "U2") (pin "26") (pinfunction "VGEN3_26") (pintype "output"))
    )
    (net (code "33") (name "Net-(C296-3)") (class "Default")
      (node (ref "C296") (pin "1") (pinfunction "3_1") (pintype "passive"))
      (node (ref "R203") (pin "1") (pintype "passive"))
      (node (ref "U2") (pin "28") (pinfunction "VGEN4_28") (pintype "output"))
    )
    (net (code "34") (name "Net-(C300-3)") (class "Default")
      (node (ref "C300") (pin "1") (pinfunction "3_1") (pintype "passive"))
      (node (ref "R217") (pin "1") (pintype "passive"))
      (node (ref "U2") (pin "39") (pinfunction "VGEN5_39") (pintype "output"))
    )
    (net (code "35") (name "Net-(C304-3)") (class "Default")
      (node (ref "C304") (pin "1") (pinfunction "3_1") (pintype "passive"))
      (node (ref "R206") (pin "1") (pintype "passive"))
      (node (ref "U2") (pin "41") (pinfunction "VGEN6_41") (pintype "output"))
    )
    (net (code "36") (name "Net-(C309-3)") (class "Default")
      (node (ref "C309") (pin "1") (pinfunction "3_1") (pintype "passive"))
      (node (ref "C310") (pin "1") (pinfunction "3_1") (pintype "passive"))
      (node (ref "L12") (pin "2") (pintype "passive"))
      (node (ref "R207") (pin "1") (pintype "passive"))
    )
    (net (code "37") (name "Net-(FB18-Pad1)") (class "Default")
      (node (ref "FB18") (pin "1") (pinfunction "1_1") (pintype "passive"))
      (node (ref "R195") (pin "1") (pintype "passive"))
    )
    (net (code "38") (name "Net-(FB20-Pad1)") (class "Default")
      (node (ref "FB20") (pin "1") (pinfunction "1_1") (pintype "passive"))
      (node (ref "R196") (pin "2") (pintype "passive"))
    )
    (net (code "39") (name "Net-(FB21-Pad1)") (class "Default")
      (node (ref "FB21") (pin "1") (pinfunction "1_1") (pintype "passive"))
      (node (ref "R198") (pin "1") (pintype "passive"))
    )
    (net (code "40") (name "Net-(FB24-Pad1)") (class "Default")
      (node (ref "FB24") (pin "1") (pinfunction "1_1") (pintype "passive"))
      (node (ref "R202") (pin "2") (pintype "passive"))
    )
    (net (code "41") (name "Net-(FB26-Pad1)") (class "Default")
      (node (ref "FB26") (pin "1") (pinfunction "1_1") (pintype "passive"))
      (node (ref "R205") (pin "2") (pintype "passive"))
    )
    (net (code "42") (name "Net-(U2A-SW1A_LX)") (class "Default")
      (node (ref "L8") (pin "1") (pintype "passive"))
      (node (ref "U2") (pin "8") (pinfunction "SW1A_LX_8") (pintype "passive"))
      (node (ref "U2") (pin "9") (pinfunction "SW1B_LX_9") (pintype "output"))
    )
    (net (code "43") (name "Net-(U2A-SW1C_LX)") (class "Default")
      (node (ref "L9") (pin "1") (pintype "passive"))
      (node (ref "U2") (pin "11") (pinfunction "SW1C_LX_11") (pintype "output"))
    )
    (net (code "44") (name "Net-(U2A-SW2_LX)") (class "Default")
      (node (ref "L10") (pin "1") (pintype "passive"))
      (node (ref "U2") (pin "22") (pinfunction "SW2_LX_22") (pintype "output"))
    )
    (net (code "45") (name "Net-(U2A-SW3A_FB)") (class "Default")
      (node (ref "FB25") (pin "1") (pinfunction "1_1") (pintype "passive"))
      (node (ref "R204") (pin "2") (pintype "passive"))
      (node (ref "U2") (pin "38") (pinfunction "SW3A_FB_38") (pintype "input"))
    )
    (net (code "46") (name "Net-(U2A-SW3A_LX)") (class "Default")
      (node (ref "L11") (pin "1") (pintype "passive"))
      (node (ref "U2") (pin "35") (pinfunction "SW3B_LX_35") (pintype "passive"))
      (node (ref "U2") (pin "36") (pinfunction "SW3A_LX_36") (pintype "output"))
    )
    (net (code "47") (name "Net-(U2A-SW4_LX)") (class "Default")
      (node (ref "L12") (pin "1") (pintype "passive"))
      (node (ref "U2") (pin "21") (pinfunction "SW4_LX_21") (pintype "output"))
    )
    (net (code "48") (name "unconnected-(U2A-SW3B_FB-Pad33)") (class "Default")
      (node (ref "U2") (pin "33") (pinfunction "SW3B_FB_33") (pintype "input+no_connect"))
    )
    (net (code "49") (name "unconnected-(U2A-SWBST_FB-Pad44)") (class "Default")
      (node (ref "U2") (pin "44") (pinfunction "SWBST_FB_44") (pintype "input+no_connect"))
    )
    (net (code "50") (name "unconnected-(U2A-SWBST_IN-Pad45)") (class "Default")
      (node (ref "U2") (pin "45") (pinfunction "SWBST_IN_45") (pintype "input+no_connect"))
    )
    (net (code "51") (name "unconnected-(U2A-SWBST_LX-Pad46)") (class "Default")
      (node (ref "U2") (pin "46") (pinfunction "SWBST_LX_46") (pintype "output+no_connect"))
    )
    (net (code "52") (name "unconnected-(U2B-VGEN1-Pad16)") (class "Default")
      (node (ref "U2") (pin "16") (pinfunction "VGEN1_16") (pintype "output+no_connect"))
    )
  )
)
